# PCB_sid_pm.net
KiCad netlist of a schematic drawn in EasyEDA
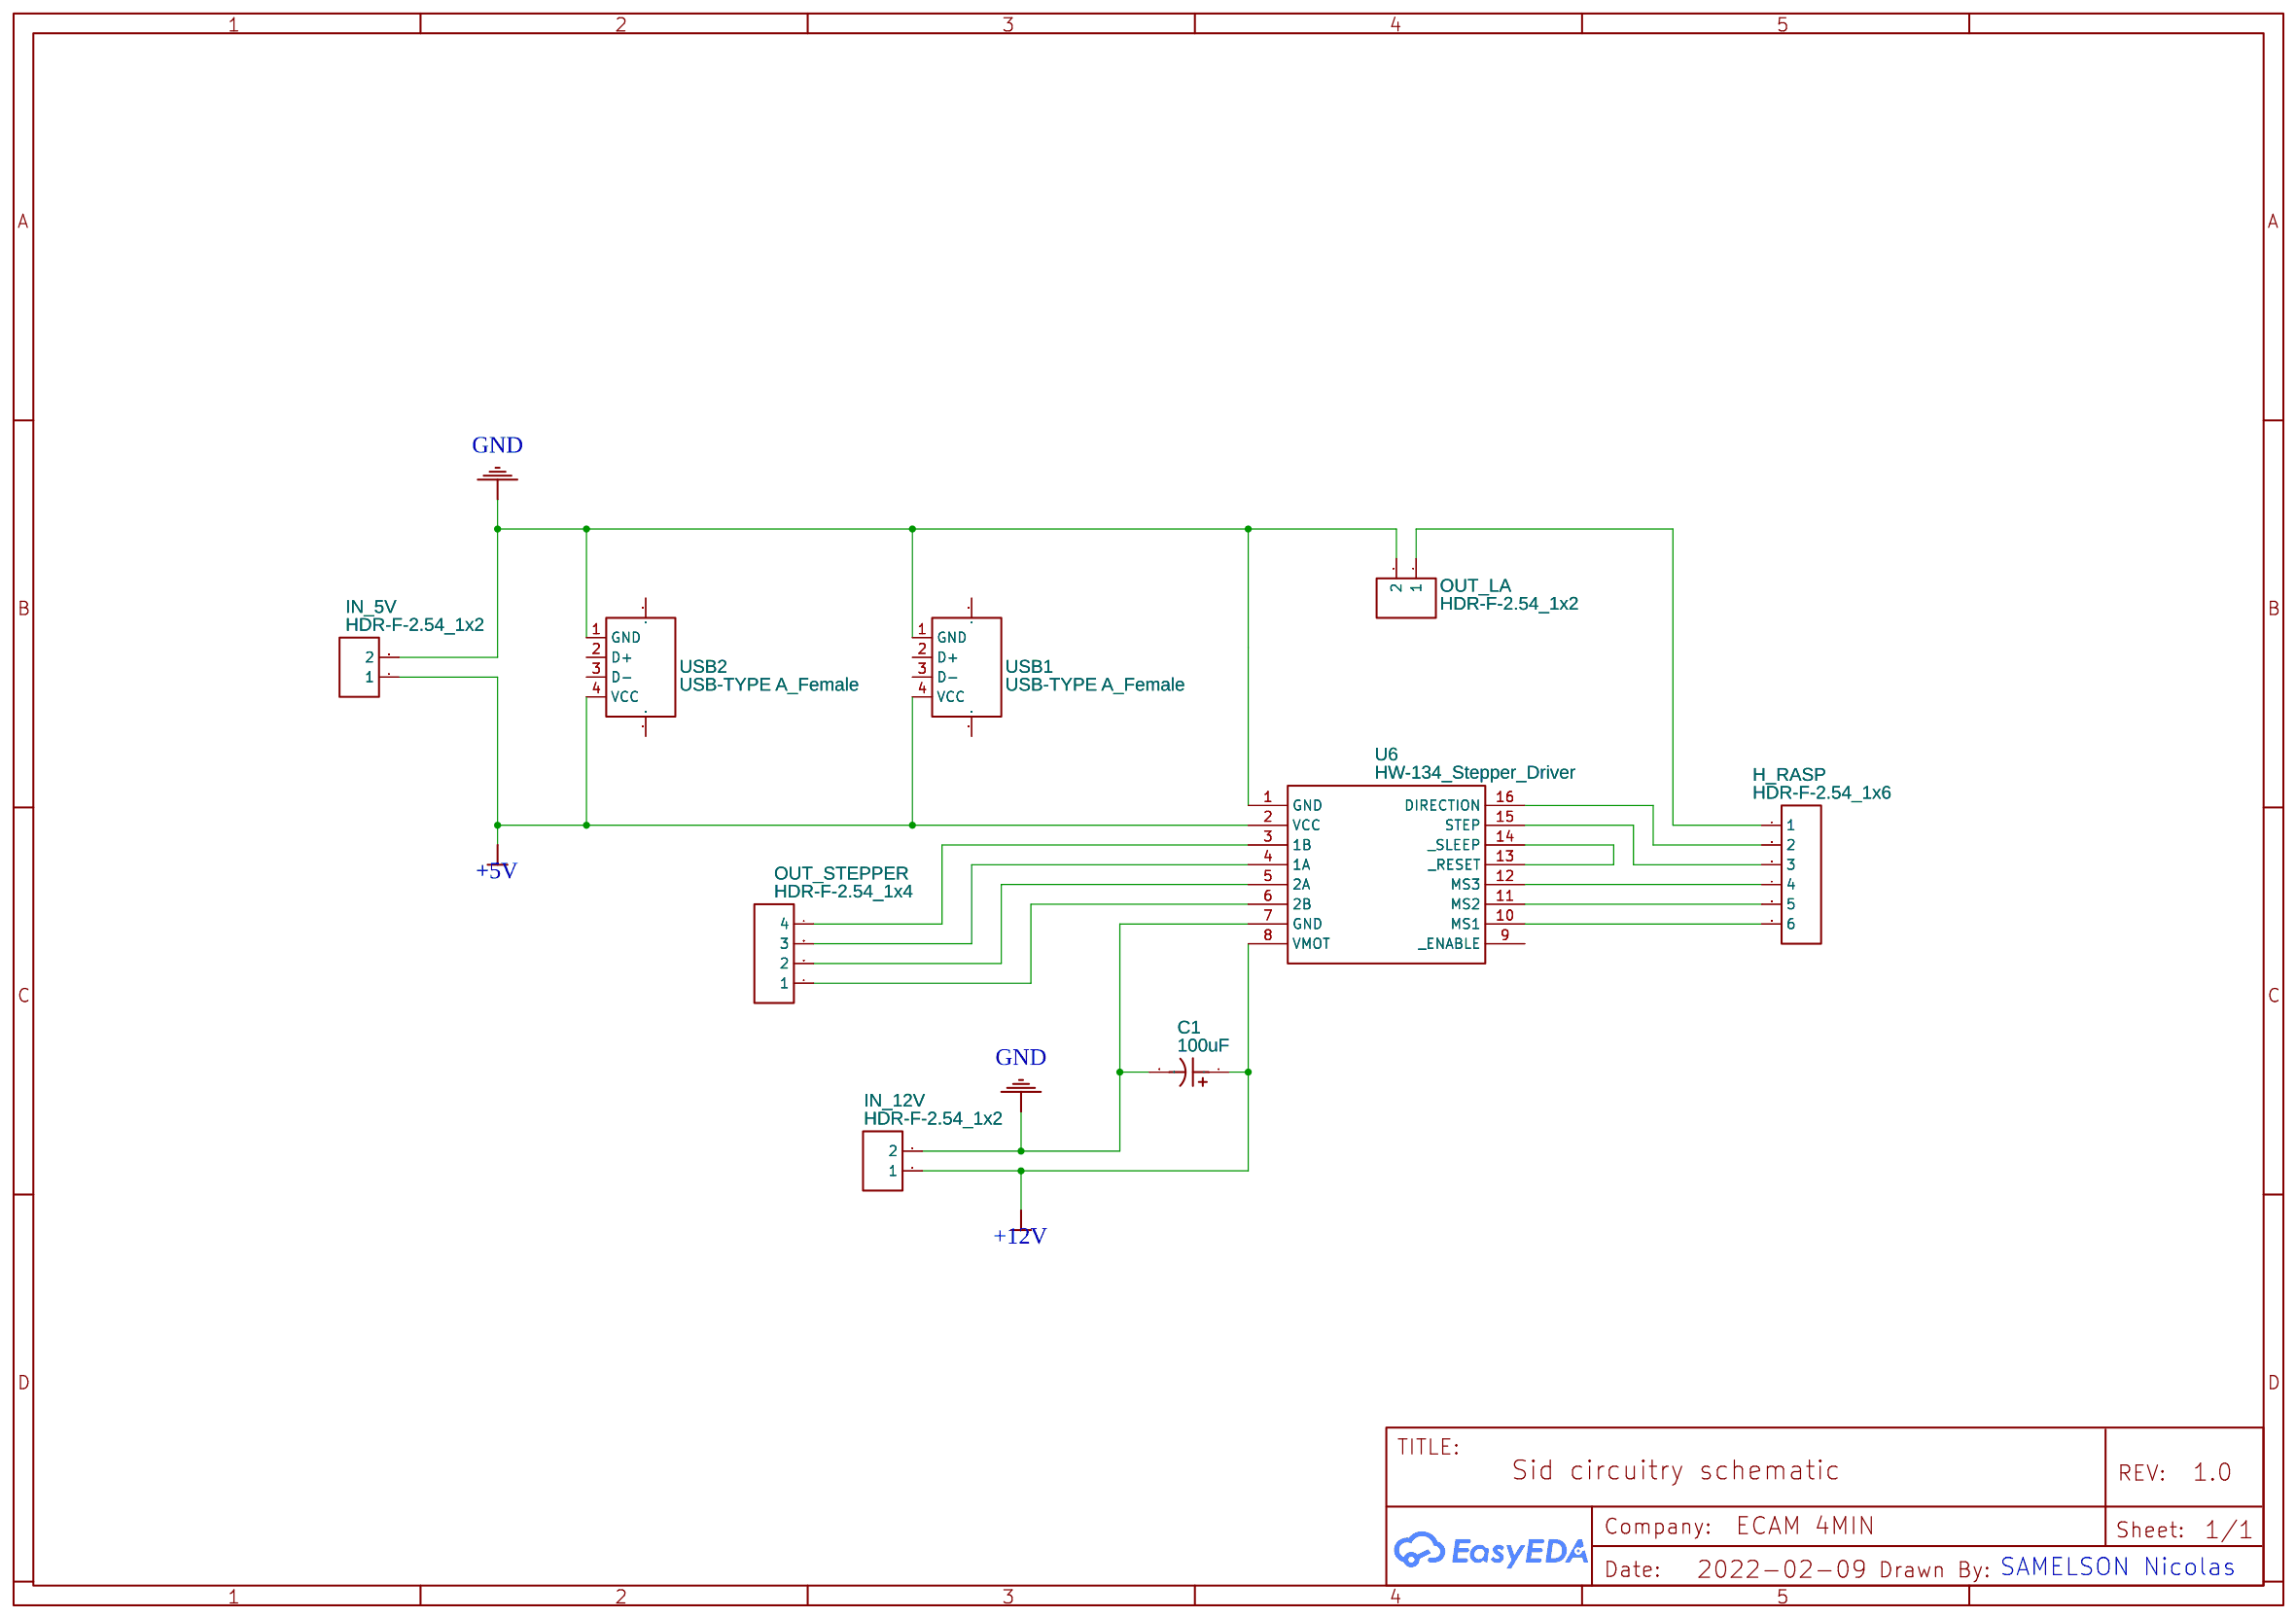
[diagram p0: schematic sheet]

(export (version "E")
  (design (tool "Eeschema 10.0.6"))
  (components
    (comp (ref "C1")
      (value "100uF")
      (fields
        (field (name "BOM_Manufacturer Part") "ECA1HHG101")
        (field (name "BOM_Supplier Part") "C713160")
      )
      (libsource (lib "") (part "ECA1HHG101"))
    )
    (comp (ref "H_RASP")
      (value "HDR-F-2.54_1x6")
      (fields (field (name "BOM_Supplier Part") "C40877"))
      (libsource (lib "") (part "HDR-F-2.54_1x6"))
    )
    (comp (ref "IN_5V")
      (value "HDR-F-2.54_1x2")
      (fields (field (name "BOM_Supplier Part") "C49661"))
      (libsource (lib "") (part "HDR-F-2.54_1x2_2"))
    )
    (comp (ref "IN_12V")
      (value "HDR-F-2.54_1x2")
      (fields (field (name "BOM_Supplier Part") "C49661"))
      (libsource (lib "") (part "HDR-F-2.54_1x2"))
    )
    (comp (ref "OUT_LA")
      (value "HDR-F-2.54_1x2")
      (fields (field (name "BOM_Supplier Part") "C49661"))
      (libsource (lib "") (part "HDR-F-2.54_1x2_1"))
    )
    (comp (ref "OUT_STEPPER")
      (value "HDR-F-2.54_1x4")
      (fields (field (name "BOM_Supplier Part") "C225501"))
      (libsource (lib "") (part "HDR-F-2.54_1x4"))
    )
    (comp (ref "U6") (value "HW-134_Stepper_Driver") (libsource (lib "") (part "HW-134_Stepper_Driver")))
    (comp (ref "USB1")
      (value "USB-TYPE A_Female")
      (fields (field (name "BOM_Supplier Part") "C42605"))
      (libsource (lib "") (part "USB-TYPE A_Female"))
    )
    (comp (ref "USB2")
      (value "USB-TYPE A_Female")
      (fields (field (name "BOM_Supplier Part") "C42605"))
      (libsource (lib "") (part "USB-TYPE A_Female"))
    )
  )
  (nets
    (net (code "1") (name "+5V") (class "Default")
      (node (ref "IN_5V") (pin "1") (pinfunction "1_1") (pintype "input"))
      (node (ref "U6") (pin "2") (pinfunction "VCC_2") (pintype "unspecified"))
      (node (ref "USB1") (pin "4") (pinfunction "VCC_4") (pintype "input"))
      (node (ref "USB2") (pin "4") (pinfunction "VCC_4") (pintype "input"))
    )
    (net (code "2") (name "+12V") (class "Default")
      (node (ref "C1") (pin "1") (pinfunction "1_1") (pintype "input"))
      (node (ref "IN_12V") (pin "1") (pinfunction "1_1") (pintype "input"))
      (node (ref "U6") (pin "8") (pinfunction "VMOT_8") (pintype "unspecified"))
    )
    (net (code "3") (name "GND") (class "Default")
      (node (ref "C1") (pin "2") (pinfunction "2_2") (pintype "input"))
      (node (ref "IN_12V") (pin "2") (pinfunction "2_2") (pintype "input"))
      (node (ref "IN_5V") (pin "2") (pinfunction "2_2") (pintype "input"))
      (node (ref "OUT_LA") (pin "2") (pinfunction "2_2") (pintype "input"))
      (node (ref "U6") (pin "1") (pinfunction "GND_1") (pintype "unspecified"))
      (node (ref "U6") (pin "7") (pinfunction "GND_7") (pintype "unspecified"))
      (node (ref "USB1") (pin "1") (pinfunction "GND_1") (pintype "input"))
      (node (ref "USB2") (pin "1") (pinfunction "GND_1") (pintype "input"))
    )
    (net (code "4") (name "Net-(H_RASP-Pad1)") (class "Default")
      (node (ref "H_RASP") (pin "1") (pinfunction "1_1") (pintype "input"))
      (node (ref "OUT_LA") (pin "1") (pinfunction "1_1") (pintype "input"))
    )
    (net (code "5") (name "Net-(U6-1A)") (class "Default")
      (node (ref "OUT_STEPPER") (pin "3") (pinfunction "3_3") (pintype "unspecified"))
      (node (ref "U6") (pin "4") (pinfunction "1A_4") (pintype "unspecified"))
    )
    (net (code "6") (name "Net-(U6-1B)") (class "Default")
      (node (ref "OUT_STEPPER") (pin "4") (pinfunction "4_4") (pintype "unspecified"))
      (node (ref "U6") (pin "3") (pinfunction "1B_3") (pintype "unspecified"))
    )
    (net (code "7") (name "Net-(U6-2A)") (class "Default")
      (node (ref "OUT_STEPPER") (pin "2") (pinfunction "2_2") (pintype "unspecified"))
      (node (ref "U6") (pin "5") (pinfunction "2A_5") (pintype "unspecified"))
    )
    (net (code "8") (name "Net-(U6-2B)") (class "Default")
      (node (ref "OUT_STEPPER") (pin "1") (pinfunction "1_1") (pintype "unspecified"))
      (node (ref "U6") (pin "6") (pinfunction "2B_6") (pintype "unspecified"))
    )
    (net (code "9") (name "Net-(U6-DIRECTION)") (class "Default")
      (node (ref "H_RASP") (pin "2") (pinfunction "2_2") (pintype "input"))
      (node (ref "U6") (pin "16") (pinfunction "DIRECTION_16") (pintype "unspecified"))
    )
    (net (code "10") (name "Net-(U6-MS1)") (class "Default")
      (node (ref "H_RASP") (pin "6") (pinfunction "6_6") (pintype "input"))
      (node (ref "U6") (pin "10") (pinfunction "MS1_10") (pintype "unspecified"))
    )
    (net (code "11") (name "Net-(U6-MS2)") (class "Default")
      (node (ref "H_RASP") (pin "5") (pinfunction "5_5") (pintype "input"))
      (node (ref "U6") (pin "11") (pinfunction "MS2_11") (pintype "unspecified"))
    )
    (net (code "12") (name "Net-(U6-MS3)") (class "Default")
      (node (ref "H_RASP") (pin "4") (pinfunction "4_4") (pintype "input"))
      (node (ref "U6") (pin "12") (pinfunction "MS3_12") (pintype "unspecified"))
    )
    (net (code "13") (name "Net-(U6-STEP)") (class "Default")
      (node (ref "H_RASP") (pin "3") (pinfunction "3_3") (pintype "input"))
      (node (ref "U6") (pin "15") (pinfunction "STEP_15") (pintype "unspecified"))
    )
    (net (code "14") (name "Net-(U6-_RESET)") (class "Default")
      (node (ref "U6") (pin "13") (pinfunction "_RESET_13") (pintype "unspecified"))
      (node (ref "U6") (pin "14") (pinfunction "_SLEEP_14") (pintype "unspecified"))
    )
    (net (code "15") (name "unconnected-(U6-_ENABLE-Pad9)") (class "Default")
      (node (ref "U6") (pin "9") (pinfunction "_ENABLE_9") (pintype "unspecified"))
    )
    (net (code "16") (name "unconnected-(USB1-D+-Pad2)") (class "Default")
      (node (ref "USB1") (pin "2") (pinfunction "D+_2") (pintype "input"))
    )
    (net (code "17") (name "unconnected-(USB1-D--Pad3)") (class "Default")
      (node (ref "USB1") (pin "3") (pinfunction "D-_3") (pintype "input"))
    )
    (net (code "18") (name "unconnected-(USB1-Pad5)") (class "Default")
      (node (ref "USB1") (pin "5") (pinfunction "5_5") (pintype "unspecified"))
    )
    (net (code "19") (name "unconnected-(USB1-Pad6)") (class "Default")
      (node (ref "USB1") (pin "6") (pinfunction "6_6") (pintype "unspecified"))
    )
    (net (code "20") (name "unconnected-(USB2-D+-Pad2)") (class "Default")
      (node (ref "USB2") (pin "2") (pinfunction "D+_2") (pintype "input"))
    )
    (net (code "21") (name "unconnected-(USB2-D--Pad3)") (class "Default")
      (node (ref "USB2") (pin "3") (pinfunction "D-_3") (pintype "input"))
    )
    (net (code "22") (name "unconnected-(USB2-Pad5)") (class "Default")
      (node (ref "USB2") (pin "5") (pinfunction "5_5") (pintype "unspecified"))
    )
    (net (code "23") (name "unconnected-(USB2-Pad6)") (class "Default")
      (node (ref "USB2") (pin "6") (pinfunction "6_6") (pintype "unspecified"))
    )
  )
)
